# 1541-3n.net
KiCad netlist of a schematic drawn in EAGLE
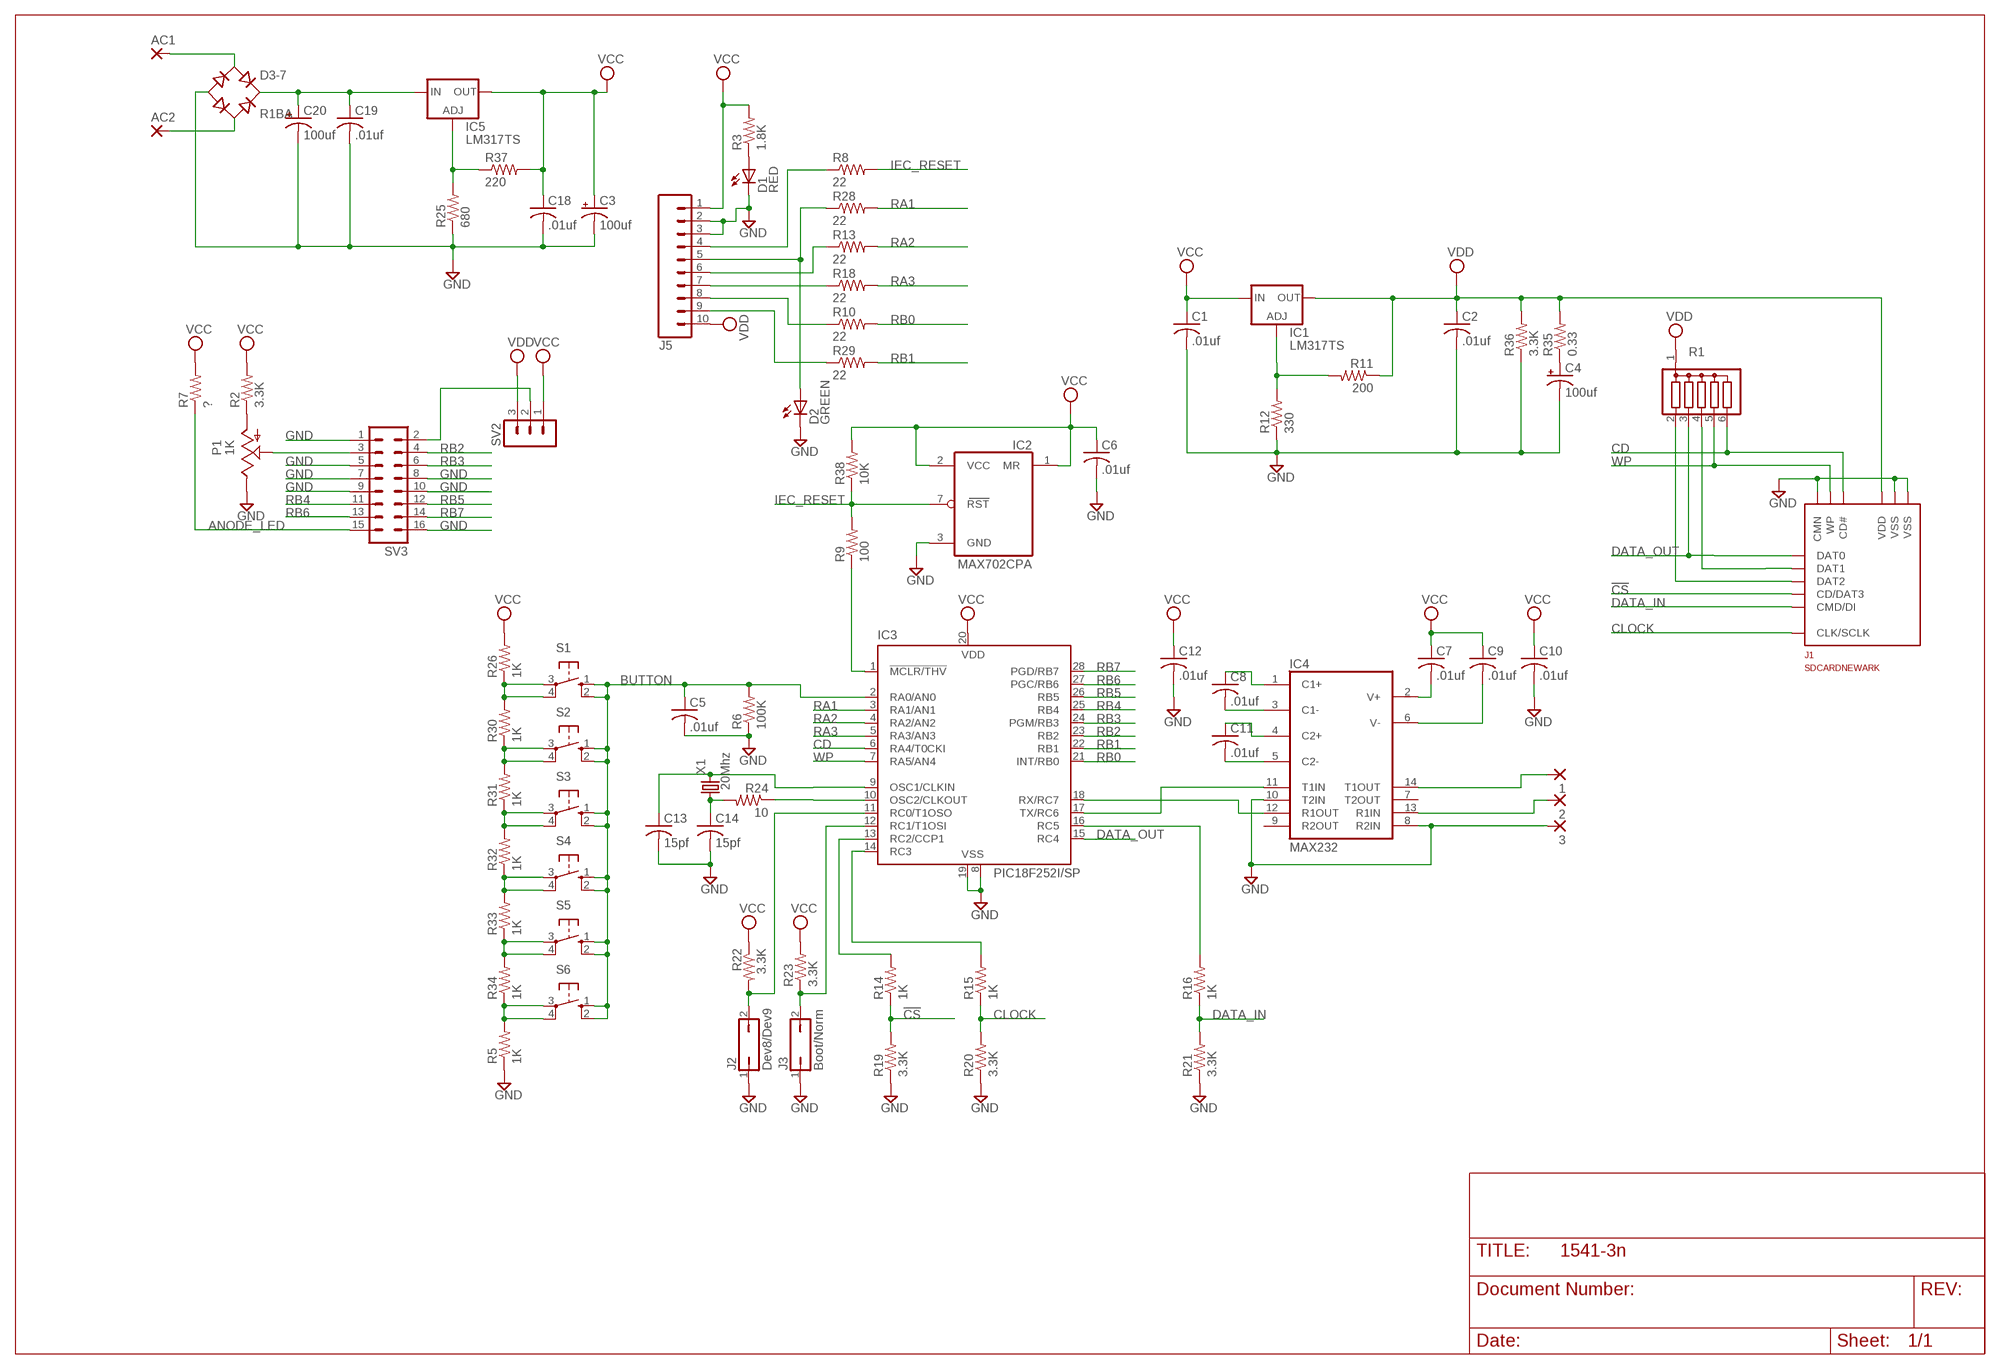
[diagram p0: schematic, sheet 1]

(export (version "E")
  (design (tool "Eeschema 10.0.6"))
  (components
    (comp (ref "1")
      (value "2,15/1,0")
      (footprint "eagle-import:2,15_1,0")
      (libsource (lib "eagle-import") (part "2,15/1,0"))
    )
    (comp (ref "2")
      (value "2,15/1,0")
      (footprint "eagle-import:2,15_1,0")
      (libsource (lib "eagle-import") (part "2,15/1,0"))
    )
    (comp (ref "3")
      (value "2,15/1,0")
      (footprint "eagle-import:2,15_1,0")
      (libsource (lib "eagle-import") (part "2,15/1,0"))
    )
    (comp (ref "AC1")
      (value "2,15/1,0")
      (footprint "eagle-import:2,15_1,0")
      (libsource (lib "eagle-import") (part "2,15/1,0"))
    )
    (comp (ref "AC2")
      (value "2,15/1,0")
      (footprint "eagle-import:2,15_1,0")
      (libsource (lib "eagle-import") (part "2,15/1,0"))
    )
    (comp (ref "C1")
      (value ".01uf")
      (footprint "eagle-import:C025-024X044")
      (libsource (lib "eagle-import") (part "C-US025-024X044"))
    )
    (comp (ref "C2")
      (value ".01uf")
      (footprint "eagle-import:C025-024X044")
      (libsource (lib "eagle-import") (part "C-US025-024X044"))
    )
    (comp (ref "C3")
      (value "100uf")
      (footprint "eagle-import:E2-5")
      (libsource (lib "eagle-import") (part "CPOL-USE2-5"))
    )
    (comp (ref "C4")
      (value "100uf")
      (footprint "eagle-import:E2-5")
      (libsource (lib "eagle-import") (part "CPOL-USE2-5"))
    )
    (comp (ref "C5")
      (value ".01uf")
      (footprint "eagle-import:C025-024X044")
      (libsource (lib "eagle-import") (part "C-US025-024X044"))
    )
    (comp (ref "C6")
      (value ".01uf")
      (footprint "eagle-import:C025-024X044")
      (libsource (lib "eagle-import") (part "C-US025-024X044"))
    )
    (comp (ref "C7")
      (value ".01uf")
      (footprint "eagle-import:C025-024X044")
      (libsource (lib "eagle-import") (part "C-US025-024X044"))
    )
    (comp (ref "C8")
      (value ".01uf")
      (footprint "eagle-import:C025-024X044")
      (libsource (lib "eagle-import") (part "C-US025-024X044"))
    )
    (comp (ref "C9")
      (value ".01uf")
      (footprint "eagle-import:C025-024X044")
      (libsource (lib "eagle-import") (part "C-US025-024X044"))
    )
    (comp (ref "C10")
      (value ".01uf")
      (footprint "eagle-import:C025-024X044")
      (libsource (lib "eagle-import") (part "C-US025-024X044"))
    )
    (comp (ref "C11")
      (value ".01uf")
      (footprint "eagle-import:C025-024X044")
      (libsource (lib "eagle-import") (part "C-US025-024X044"))
    )
    (comp (ref "C12")
      (value ".01uf")
      (footprint "eagle-import:C025-024X044")
      (libsource (lib "eagle-import") (part "C-US025-024X044"))
    )
    (comp (ref "C13")
      (value "15pf")
      (footprint "eagle-import:C025-024X044")
      (libsource (lib "eagle-import") (part "C-US025-024X044"))
    )
    (comp (ref "C14")
      (value "15pf")
      (footprint "eagle-import:C025-024X044")
      (libsource (lib "eagle-import") (part "C-US025-024X044"))
    )
    (comp (ref "C18")
      (value ".01uf")
      (footprint "eagle-import:C025-024X044")
      (libsource (lib "eagle-import") (part "C-US025-024X044"))
    )
    (comp (ref "C19")
      (value ".01uf")
      (footprint "eagle-import:C025-024X044")
      (libsource (lib "eagle-import") (part "C-US025-024X044"))
    )
    (comp (ref "C20")
      (value "100uf")
      (footprint "eagle-import:E2-5")
      (libsource (lib "eagle-import") (part "CPOL-USE2-5"))
    )
    (comp (ref "D1")
      (value "RED")
      (footprint "eagle-import:LED3MM")
      (libsource (lib "eagle-import") (part "LED3MM"))
    )
    (comp (ref "D2")
      (value "GREEN")
      (footprint "eagle-import:LED3MM")
      (libsource (lib "eagle-import") (part "LED3MM"))
    )
    (comp (ref "D3-7")
      (value "R1BA")
      (footprint "eagle-import:RB1A")
      (libsource (lib "eagle-import") (part "RB1A"))
    )
    (comp (ref "IC1")
      (value "LM317TS")
      (footprint "eagle-import:317TS")
      (libsource (lib "eagle-import") (part "LM317TS"))
    )
    (comp (ref "IC2")
      (value "MAX702CPA")
      (footprint "eagle-import:DIL08")
      (fields (field (name "MF") "MAXIM") (field (name "MPN") "MAX702CPA+"))
      (libsource (lib "eagle-import") (part "MAX702CPA"))
    )
    (comp (ref "IC3")
      (value "PIC18F252I/SP")
      (footprint "eagle-import:DIL28-3")
      (fields (field (name "MF") "MICROCHIP") (field (name "MPN") "PIC16F870-I/SP"))
      (libsource (lib "eagle-import") (part "PIC16870PF"))
    )
    (comp (ref "IC4")
      (value "MAX232")
      (footprint "eagle-import:DIL16")
      (fields (field (name "MF") "MAXIM") (field (name "MPN") "MAX232ACPE+"))
      (libsource (lib "eagle-import") (part "MAX232"))
    )
    (comp (ref "IC5")
      (value "LM317TS")
      (footprint "eagle-import:317TS")
      (libsource (lib "eagle-import") (part "LM317TS"))
    )
    (comp (ref "J1")
      (value "SDCARDNEWARK")
      (footprint "eagle-import:SDBMF-00915B0T2")
      (libsource (lib "eagle-import") (part "SDCARDNEWARK"))
    )
    (comp (ref "J2")
      (value "Dev8/Dev9")
      (footprint "eagle-import:JP1")
      (libsource (lib "eagle-import") (part "JP1Q"))
    )
    (comp (ref "J3")
      (value "Boot/Norm")
      (footprint "eagle-import:JP1")
      (libsource (lib "eagle-import") (part "JP1Q"))
    )
    (comp (ref "J5")
      (value "M10")
      (footprint "eagle-import:10P")
      (libsource (lib "eagle-import") (part "M10"))
    )
    (comp (ref "P1")
      (value "1K")
      (footprint "eagle-import:LI10")
      (libsource (lib "eagle-import") (part "TRIM_US-LI10"))
    )
    (comp (ref "R1")
      (value "G05R")
      (footprint "eagle-import:SIL6")
      (libsource (lib "eagle-import") (part "G05R"))
    )
    (comp (ref "R2")
      (value "3.3K")
      (footprint "eagle-import:0207_2V")
      (libsource (lib "eagle-import") (part "R-US_0207/2V"))
    )
    (comp (ref "R3")
      (value "1.8K")
      (footprint "eagle-import:0207_2V")
      (libsource (lib "eagle-import") (part "R-US_0207/2V"))
    )
    (comp (ref "R5")
      (value "1K")
      (footprint "eagle-import:0207_2V")
      (libsource (lib "eagle-import") (part "R-US_0207/2V"))
    )
    (comp (ref "R6")
      (value "100K")
      (footprint "eagle-import:0207_2V")
      (libsource (lib "eagle-import") (part "R-US_0207/2V"))
    )
    (comp (ref "R7")
      (value "?")
      (footprint "eagle-import:0207_2V")
      (libsource (lib "eagle-import") (part "R-US_0207/2V"))
    )
    (comp (ref "R8")
      (value "22")
      (footprint "eagle-import:0207_2V")
      (libsource (lib "eagle-import") (part "R-US_0207/2V"))
    )
    (comp (ref "R9")
      (value "100")
      (footprint "eagle-import:0207_2V")
      (libsource (lib "eagle-import") (part "R-US_0207/2V"))
    )
    (comp (ref "R10")
      (value "22")
      (footprint "eagle-import:0207_2V")
      (libsource (lib "eagle-import") (part "R-US_0207/2V"))
    )
    (comp (ref "R11")
      (value "200")
      (footprint "eagle-import:0207_2V")
      (libsource (lib "eagle-import") (part "R-US_0207/2V"))
    )
    (comp (ref "R12")
      (value "330")
      (footprint "eagle-import:0207_2V")
      (libsource (lib "eagle-import") (part "R-US_0207/2V"))
    )
    (comp (ref "R13")
      (value "22")
      (footprint "eagle-import:0207_2V")
      (libsource (lib "eagle-import") (part "R-US_0207/2V"))
    )
    (comp (ref "R14")
      (value "1K")
      (footprint "eagle-import:0207_2V")
      (libsource (lib "eagle-import") (part "R-US_0207/2V"))
    )
    (comp (ref "R15")
      (value "1K")
      (footprint "eagle-import:0207_2V")
      (libsource (lib "eagle-import") (part "R-US_0207/2V"))
    )
    (comp (ref "R16")
      (value "1K")
      (footprint "eagle-import:0207_2V")
      (libsource (lib "eagle-import") (part "R-US_0207/2V"))
    )
    (comp (ref "R18")
      (value "22")
      (footprint "eagle-import:0207_2V")
      (libsource (lib "eagle-import") (part "R-US_0207/2V"))
    )
    (comp (ref "R19")
      (value "3.3K")
      (footprint "eagle-import:0207_2V")
      (libsource (lib "eagle-import") (part "R-US_0207/2V"))
    )
    (comp (ref "R20")
      (value "3.3K")
      (footprint "eagle-import:0207_2V")
      (libsource (lib "eagle-import") (part "R-US_0207/2V"))
    )
    (comp (ref "R21")
      (value "3.3K")
      (footprint "eagle-import:0207_2V")
      (libsource (lib "eagle-import") (part "R-US_0207/2V"))
    )
    (comp (ref "R22")
      (value "3.3K")
      (footprint "eagle-import:0207_2V")
      (libsource (lib "eagle-import") (part "R-US_0207/2V"))
    )
    (comp (ref "R23")
      (value "3.3K")
      (footprint "eagle-import:0207_2V")
      (libsource (lib "eagle-import") (part "R-US_0207/2V"))
    )
    (comp (ref "R24")
      (value "10")
      (footprint "eagle-import:0207_2V")
      (libsource (lib "eagle-import") (part "R-US_0207/2V"))
    )
    (comp (ref "R25")
      (value "680")
      (footprint "eagle-import:0207_2V")
      (libsource (lib "eagle-import") (part "R-US_0207/2V"))
    )
    (comp (ref "R26")
      (value "1K")
      (footprint "eagle-import:0207_2V")
      (libsource (lib "eagle-import") (part "R-US_0207/2V"))
    )
    (comp (ref "R28")
      (value "22")
      (footprint "eagle-import:0207_2V")
      (libsource (lib "eagle-import") (part "R-US_0207/2V"))
    )
    (comp (ref "R29")
      (value "22")
      (footprint "eagle-import:0207_2V")
      (libsource (lib "eagle-import") (part "R-US_0207/2V"))
    )
    (comp (ref "R30")
      (value "1K")
      (footprint "eagle-import:0207_2V")
      (libsource (lib "eagle-import") (part "R-US_0207/2V"))
    )
    (comp (ref "R31")
      (value "1K")
      (footprint "eagle-import:0207_2V")
      (libsource (lib "eagle-import") (part "R-US_0207/2V"))
    )
    (comp (ref "R32")
      (value "1K")
      (footprint "eagle-import:0207_2V")
      (libsource (lib "eagle-import") (part "R-US_0207/2V"))
    )
    (comp (ref "R33")
      (value "1K")
      (footprint "eagle-import:0207_2V")
      (libsource (lib "eagle-import") (part "R-US_0207/2V"))
    )
    (comp (ref "R34")
      (value "1K")
      (footprint "eagle-import:0207_2V")
      (libsource (lib "eagle-import") (part "R-US_0207/2V"))
    )
    (comp (ref "R35")
      (value "0.33")
      (footprint "eagle-import:0207_2V")
      (libsource (lib "eagle-import") (part "R-US_0207/2V"))
    )
    (comp (ref "R36")
      (value "3.3K")
      (footprint "eagle-import:0207_2V")
      (libsource (lib "eagle-import") (part "R-US_0207/2V"))
    )
    (comp (ref "R37")
      (value "220")
      (footprint "eagle-import:0207_2V")
      (libsource (lib "eagle-import") (part "R-US_0207/2V"))
    )
    (comp (ref "R38")
      (value "10K")
      (footprint "eagle-import:0207_2V")
      (libsource (lib "eagle-import") (part "R-US_0207/2V"))
    )
    (comp (ref "S1")
      (value "10-XX")
      (footprint "eagle-import:B3F-10XX")
      (fields (field (name "MPN") "B3F-1000"))
      (libsource (lib "eagle-import") (part "10-XX"))
    )
    (comp (ref "S2")
      (value "10-XX")
      (footprint "eagle-import:B3F-10XX")
      (fields (field (name "MPN") "B3F-1000"))
      (libsource (lib "eagle-import") (part "10-XX"))
    )
    (comp (ref "S3")
      (value "10-XX")
      (footprint "eagle-import:B3F-10XX")
      (fields (field (name "MPN") "B3F-1000"))
      (libsource (lib "eagle-import") (part "10-XX"))
    )
    (comp (ref "S4")
      (value "10-XX")
      (footprint "eagle-import:B3F-10XX")
      (fields (field (name "MPN") "B3F-1000"))
      (libsource (lib "eagle-import") (part "10-XX"))
    )
    (comp (ref "S5")
      (value "10-XX")
      (footprint "eagle-import:B3F-10XX")
      (fields (field (name "MPN") "B3F-1000"))
      (libsource (lib "eagle-import") (part "10-XX"))
    )
    (comp (ref "S6")
      (value "10-XX")
      (footprint "eagle-import:B3F-10XX")
      (fields (field (name "MPN") "B3F-1000"))
      (libsource (lib "eagle-import") (part "10-XX"))
    )
    (comp (ref "SV2")
      (value "MA03-1")
      (footprint "eagle-import:MA03-1")
      (libsource (lib "eagle-import") (part "MA03-1"))
    )
    (comp (ref "SV3")
      (value "ML16")
      (footprint "eagle-import:ML16")
      (libsource (lib "eagle-import") (part "ML16"))
    )
    (comp (ref "X1")
      (value "20Mhz")
      (footprint "eagle-import:HC49U70")
      (libsource (lib "eagle-import") (part "CRYSTALHC49U70"))
    )
  )
  (nets
    (net (code "1") (name "/ANODE_LED") (class "Default")
      (node (ref "R7") (pin "1") (pinfunction "1_1") (pintype "passive"))
      (node (ref "SV3") (pin "15") (pinfunction "15_15") (pintype "passive"))
    )
    (net (code "2") (name "/BUTTON") (class "Default")
      (node (ref "C5") (pin "1") (pinfunction "1_1") (pintype "passive"))
      (node (ref "IC3") (pin "2") (pinfunction "RA0/AN0_2") (pintype "bidirectional"))
      (node (ref "R6") (pin "2") (pinfunction "2_2") (pintype "passive"))
      (node (ref "S1") (pin "1") (pinfunction "S_1") (pintype "passive"))
      (node (ref "S1") (pin "2") (pinfunction "S1_2") (pintype "passive"))
      (node (ref "S2") (pin "1") (pinfunction "S_1") (pintype "passive"))
      (node (ref "S2") (pin "2") (pinfunction "S1_2") (pintype "passive"))
      (node (ref "S3") (pin "1") (pinfunction "S_1") (pintype "passive"))
      (node (ref "S3") (pin "2") (pinfunction "S1_2") (pintype "passive"))
      (node (ref "S4") (pin "1") (pinfunction "S_1") (pintype "passive"))
      (node (ref "S4") (pin "2") (pinfunction "S1_2") (pintype "passive"))
      (node (ref "S5") (pin "1") (pinfunction "S_1") (pintype "passive"))
      (node (ref "S5") (pin "2") (pinfunction "S1_2") (pintype "passive"))
      (node (ref "S6") (pin "1") (pinfunction "S_1") (pintype "passive"))
      (node (ref "S6") (pin "2") (pinfunction "S1_2") (pintype "passive"))
    )
    (net (code "3") (name "/CD") (class "Default")
      (node (ref "IC3") (pin "6") (pinfunction "RA4/T0CKI_6") (pintype "bidirectional"))
      (node (ref "J1") (pin "SW1") (pinfunction "CD#_SW1") (pintype "output"))
      (node (ref "R1") (pin "6") (pinfunction "6_6") (pintype "passive"))
    )
    (net (code "4") (name "/CLOCK") (class "Default")
      (node (ref "J1") (pin "CLK") (pinfunction "CLK/SCLK_CLK") (pintype "bidirectional"))
      (node (ref "R15") (pin "1") (pinfunction "1_1") (pintype "passive"))
      (node (ref "R20") (pin "2") (pinfunction "2_2") (pintype "passive"))
    )
    (net (code "5") (name "/DATA_IN") (class "Default")
      (node (ref "J1") (pin "CMD") (pinfunction "CMD/DI_CMD") (pintype "bidirectional"))
      (node (ref "R16") (pin "1") (pinfunction "1_1") (pintype "passive"))
      (node (ref "R21") (pin "2") (pinfunction "2_2") (pintype "passive"))
    )
    (net (code "6") (name "/DATA_OUT") (class "Default")
      (node (ref "IC3") (pin "15") (pinfunction "RC4_15") (pintype "bidirectional"))
      (node (ref "J1") (pin "DAT0") (pinfunction "DAT0_DAT0") (pintype "bidirectional"))
      (node (ref "R1") (pin "3") (pinfunction "3_3") (pintype "passive"))
    )
    (net (code "7") (name "/IEC_RESET") (class "Default")
      (node (ref "IC2") (pin "7") (pinfunction "RST_7") (pintype "output"))
      (node (ref "R38") (pin "1") (pinfunction "1_1") (pintype "passive"))
      (node (ref "R8") (pin "2") (pinfunction "2_2") (pintype "passive"))
      (node (ref "R9") (pin "2") (pinfunction "2_2") (pintype "passive"))
    )
    (net (code "8") (name "/RA1") (class "Default")
      (node (ref "IC3") (pin "3") (pinfunction "RA1/AN1_3") (pintype "bidirectional"))
      (node (ref "R28") (pin "2") (pinfunction "2_2") (pintype "passive"))
    )
    (net (code "9") (name "/RA2") (class "Default")
      (node (ref "IC3") (pin "4") (pinfunction "RA2/AN2_4") (pintype "bidirectional"))
      (node (ref "R13") (pin "2") (pinfunction "2_2") (pintype "passive"))
    )
    (net (code "10") (name "/RA3") (class "Default")
      (node (ref "IC3") (pin "5") (pinfunction "RA3/AN3_5") (pintype "bidirectional"))
      (node (ref "R18") (pin "2") (pinfunction "2_2") (pintype "passive"))
    )
    (net (code "11") (name "/RB0") (class "Default")
      (node (ref "IC3") (pin "21") (pinfunction "INT/RB0_21") (pintype "bidirectional"))
      (node (ref "R10") (pin "2") (pinfunction "2_2") (pintype "passive"))
    )
    (net (code "12") (name "/RB1") (class "Default")
      (node (ref "IC3") (pin "22") (pinfunction "RB1_22") (pintype "bidirectional"))
      (node (ref "R29") (pin "2") (pinfunction "2_2") (pintype "passive"))
    )
    (net (code "13") (name "/RB2") (class "Default")
      (node (ref "IC3") (pin "23") (pinfunction "RB2_23") (pintype "bidirectional"))
      (node (ref "SV3") (pin "4") (pinfunction "4_4") (pintype "passive"))
    )
    (net (code "14") (name "/RB3") (class "Default")
      (node (ref "IC3") (pin "24") (pinfunction "PGM/RB3_24") (pintype "bidirectional"))
      (node (ref "SV3") (pin "6") (pinfunction "6_6") (pintype "passive"))
    )
    (net (code "15") (name "/RB4") (class "Default")
      (node (ref "IC3") (pin "25") (pinfunction "RB4_25") (pintype "bidirectional"))
      (node (ref "SV3") (pin "11") (pinfunction "11_11") (pintype "passive"))
    )
    (net (code "16") (name "/RB5") (class "Default")
      (node (ref "IC3") (pin "26") (pinfunction "RB5_26") (pintype "bidirectional"))
      (node (ref "SV3") (pin "12") (pinfunction "12_12") (pintype "passive"))
    )
    (net (code "17") (name "/RB6") (class "Default")
      (node (ref "IC3") (pin "27") (pinfunction "PGC/RB6_27") (pintype "bidirectional"))
      (node (ref "SV3") (pin "13") (pinfunction "13_13") (pintype "passive"))
    )
    (net (code "18") (name "/RB7") (class "Default")
      (node (ref "IC3") (pin "28") (pinfunction "PGD/RB7_28") (pintype "bidirectional"))
      (node (ref "SV3") (pin "14") (pinfunction "14_14") (pintype "passive"))
    )
    (net (code "19") (name "/WP") (class "Default")
      (node (ref "IC3") (pin "7") (pinfunction "RA5/AN4_7") (pintype "bidirectional"))
      (node (ref "J1") (pin "SW2") (pinfunction "WP_SW2") (pintype "output"))
      (node (ref "R1") (pin "5") (pinfunction "5_5") (pintype "passive"))
    )
    (net (code "20") (name "/~{CS}") (class "Default")
      (node (ref "J1") (pin "DAT3") (pinfunction "CD/DAT3_DAT3") (pintype "bidirectional"))
      (node (ref "R14") (pin "1") (pinfunction "1_1") (pintype "passive"))
      (node (ref "R19") (pin "2") (pinfunction "2_2") (pintype "passive"))
    )
    (net (code "21") (name "GND") (class "Default")
      (node (ref "3") (pin "1") (pinfunction "P_1") (pintype "passive"))
      (node (ref "C1") (pin "2") (pinfunction "2_2") (pintype "passive"))
      (node (ref "C10") (pin "2") (pinfunction "2_2") (pintype "passive"))
      (node (ref "C12") (pin "2") (pinfunction "2_2") (pintype "passive"))
      (node (ref "C13") (pin "2") (pinfunction "2_2") (pintype "passive"))
      (node (ref "C14") (pin "2") (pinfunction "2_2") (pintype "passive"))
      (node (ref "C18") (pin "2") (pinfunction "2_2") (pintype "passive"))
      (node (ref "C19") (pin "2") (pinfunction "2_2") (pintype "passive"))
      (node (ref "C2") (pin "2") (pinfunction "2_2") (pintype "passive"))
      (node (ref "C20") (pin "-") (pinfunction "-_-") (pintype "passive"))
      (node (ref "C3") (pin "-") (pinfunction "-_-") (pintype "passive"))
      (node (ref "C4") (pin "-") (pinfunction "-_-") (pintype "passive"))
      (node (ref "C5") (pin "2") (pinfunction "2_2") (pintype "passive"))
      (node (ref "C6") (pin "2") (pinfunction "2_2") (pintype "passive"))
      (node (ref "D1") (pin "K") (pinfunction "C_K") (pintype "passive"))
      (node (ref "D2") (pin "K") (pinfunction "C_K") (pintype "passive"))
      (node (ref "D3-7") (pin "-") (pinfunction "-_-") (pintype "passive"))
      (node (ref "IC2") (pin "3") (pinfunction "GND_3") (pintype "power_in"))
      (node (ref "IC3") (pin "19") (pinfunction "VSS_19") (pintype "power_in"))
      (node (ref "IC3") (pin "8") (pinfunction "VSS_8") (pintype "power_in"))
      (node (ref "IC4") (pin "10") (pinfunction "T2IN_10") (pintype "input"))
      (node (ref "IC4") (pin "8") (pinfunction "R2IN_8") (pintype "input"))
      (node (ref "J1") (pin "SW3") (pinfunction "CMN_SW3") (pintype "input"))
      (node (ref "J1") (pin "VSS$1") (pinfunction "VSS_VSS$1") (pintype "power_in"))
      (node (ref "J1") (pin "VSS$2") (pinfunction "VSS_VSS$2") (pintype "power_in"))
      (node (ref "J2") (pin "1") (pinfunction "1_1") (pintype "passive"))
      (node (ref "J3") (pin "1") (pinfunction "1_1") (pintype "passive"))
      (node (ref "J5") (pin "2") (pinfunction "2_2") (pintype "passive"))
      (node (ref "J5") (pin "3") (pinfunction "3_3") (pintype "passive"))
      (node (ref "P1") (pin "E") (pinfunction "E_E") (pintype "passive"))
      (node (ref "R12") (pin "1") (pinfunction "1_1") (pintype "passive"))
      (node (ref "R19") (pin "1") (pinfunction "1_1") (pintype "passive"))
      (node (ref "R20") (pin "1") (pinfunction "1_1") (pintype "passive"))
      (node (ref "R21") (pin "1") (pinfunction "1_1") (pintype "passive"))
      (node (ref "R25") (pin "1") (pinfunction "1_1") (pintype "passive"))
      (node (ref "R36") (pin "1") (pinfunction "1_1") (pintype "passive"))
      (node (ref "R5") (pin "1") (pinfunction "1_1") (pintype "passive"))
      (node (ref "R6") (pin "1") (pinfunction "1_1") (pintype "passive"))
      (node (ref "SV3") (pin "1") (pinfunction "1_1") (pintype "passive"))
      (node (ref "SV3") (pin "10") (pinfunction "10_10") (pintype "passive"))
      (node (ref "SV3") (pin "16") (pinfunction "16_16") (pintype "passive"))
      (node (ref "SV3") (pin "5") (pinfunction "5_5") (pintype "passive"))
      (node (ref "SV3") (pin "7") (pinfunction "7_7") (pintype "passive"))
      (node (ref "SV3") (pin "8") (pinfunction "8_8") (pintype "passive"))
      (node (ref "SV3") (pin "9") (pinfunction "9_9") (pintype "passive"))
    )
    (net (code "22") (name "Net-(1-P)") (class "Default")
      (node (ref "1") (pin "1") (pinfunction "P_1") (pintype "passive"))
      (node (ref "IC4") (pin "14") (pinfunction "T1OUT_14") (pintype "output"))
    )
    (net (code "23") (name "Net-(2-P)") (class "Default")
      (node (ref "2") (pin "1") (pinfunction "P_1") (pintype "passive"))
      (node (ref "IC4") (pin "13") (pinfunction "R1IN_13") (pintype "input"))
    )
    (net (code "24") (name "Net-(AC1-P)") (class "Default")
      (node (ref "AC1") (pin "1") (pinfunction "P_1") (pintype "passive"))
      (node (ref "D3-7") (pin "AC1") (pinfunction "AC1_AC1") (pintype "passive"))
    )
    (net (code "25") (name "Net-(AC2-P)") (class "Default")
      (node (ref "AC2") (pin "1") (pinfunction "P_1") (pintype "passive"))
      (node (ref "D3-7") (pin "AC2") (pinfunction "AC2_AC2") (pintype "passive"))
    )
    (net (code "26") (name "Net-(C4-Pad+)") (class "Default")
      (node (ref "C4") (pin "+") (pinfunction "+_+") (pintype "passive"))
      (node (ref "R35") (pin "1") (pinfunction "1_1") (pintype "passive"))
    )
    (net (code "27") (name "Net-(C14-Pad1)") (class "Default")
      (node (ref "C14") (pin "1") (pinfunction "1_1") (pintype "passive"))
      (node (ref "R24") (pin "2") (pinfunction "2_2") (pintype "passive"))
      (node (ref "X1") (pin "1") (pinfunction "1_1") (pintype "passive"))
    )
    (net (code "28") (name "Net-(D1-PadA)") (class "Default")
      (node (ref "D1") (pin "A") (pinfunction "A_A") (pintype "passive"))
      (node (ref "R3") (pin "1") (pinfunction "1_1") (pintype "passive"))
    )
    (net (code "29") (name "Net-(D2-PadA)") (class "Default")
      (node (ref "D2") (pin "A") (pinfunction "A_A") (pintype "passive"))
      (node (ref "J5") (pin "5") (pinfunction "5_5") (pintype "passive"))
      (node (ref "R28") (pin "1") (pinfunction "1_1") (pintype "passive"))
    )
    (net (code "30") (name "Net-(IC1-ADJ)") (class "Default")
      (node (ref "IC1") (pin "1") (pinfunction "ADJ_1") (pintype "input"))
      (node (ref "R11") (pin "2") (pinfunction "2_2") (pintype "passive"))
      (node (ref "R12") (pin "2") (pinfunction "2_2") (pintype "passive"))
    )
    (net (code "31") (name "Net-(IC3-OSC1{slash}CLKIN)") (class "Default")
      (node (ref "C13") (pin "1") (pinfunction "1_1") (pintype "passive"))
      (node (ref "IC3") (pin "9") (pinfunction "OSC1/CLKIN_9") (pintype "input"))
      (node (ref "X1") (pin "2") (pinfunction "2_2") (pintype "passive"))
    )
    (net (code "32") (name "Net-(IC3-OSC2{slash}CLKOUT)") (class "Default")
      (node (ref "IC3") (pin "10") (pinfunction "OSC2/CLKOUT_10") (pintype "output"))
      (node (ref "R24") (pin "1") (pinfunction "1_1") (pintype "passive"))
    )
    (net (code "33") (name "Net-(IC3-RC0{slash}T1OSO)") (class "Default")
      (node (ref "IC3") (pin "11") (pinfunction "RC0/T1OSO_11") (pintype "bidirectional"))
      (node (ref "J2") (pin "2") (pinfunction "2_2") (pintype "passive"))
      (node (ref "R22") (pin "2") (pinfunction "2_2") (pintype "passive"))
    )
    (net (code "34") (name "Net-(IC3-RC1{slash}T1OSI)") (class "Default")
      (node (ref "IC3") (pin "12") (pinfunction "RC1/T1OSI_12") (pintype "bidirectional"))
      (node (ref "J3") (pin "2") (pinfunction "2_2") (pintype "passive"))
      (node (ref "R23") (pin "1") (pinfunction "1_1") (pintype "passive"))
    )
    (net (code "35") (name "Net-(IC3-RC2{slash}CCP1)") (class "Default")
      (node (ref "IC3") (pin "13") (pinfunction "RC2/CCP1_13") (pintype "bidirectional"))
      (node (ref "R14") (pin "2") (pinfunction "2_2") (pintype "passive"))
    )
    (net (code "36") (name "Net-(IC3-RC3)") (class "Default")
      (node (ref "IC3") (pin "14") (pinfunction "RC3_14") (pintype "bidirectional"))
      (node (ref "R15") (pin "2") (pinfunction "2_2") (pintype "passive"))
    )
    (net (code "37") (name "Net-(IC3-RC5)") (class "Default")
      (node (ref "IC3") (pin "16") (pinfunction "RC5_16") (pintype "bidirectional"))
      (node (ref "R16") (pin "2") (pinfunction "2_2") (pintype "passive"))
    )
    (net (code "38") (name "Net-(IC3-RX{slash}RC7)") (class "Default")
      (node (ref "IC3") (pin "18") (pinfunction "RX/RC7_18") (pintype "bidirectional"))
      (node (ref "IC4") (pin "12") (pinfunction "R1OUT_12") (pintype "output"))
    )
    (net (code "39") (name "Net-(IC3-TX{slash}RC6)") (class "Default")
      (node (ref "IC3") (pin "17") (pinfunction "TX/RC6_17") (pintype "bidirectional"))
      (node (ref "IC4") (pin "11") (pinfunction "T1IN_11") (pintype "input"))
    )
    (net (code "40") (name "Net-(IC3-~{MCLR{slash}THV})") (class "Default")
      (node (ref "IC3") (pin "1") (pinfunction "~{MCLR/THV}_1") (pintype "input"))
      (node (ref "R9") (pin "1") (pinfunction "1_1") (pintype "passive"))
    )
    (net (code "41") (name "Net-(IC4A-C1+)") (class "Default")
      (node (ref "C8") (pin "1") (pinfunction "1_1") (pintype "passive"))
      (node (ref "IC4") (pin "1") (pinfunction "C1+_1") (pintype "bidirectional"))
    )
    (net (code "42") (name "Net-(IC4A-C1-)") (class "Default")
      (node (ref "C8") (pin "2") (pinfunction "2_2") (pintype "passive"))
      (node (ref "IC4") (pin "3") (pinfunction "C1-_3") (pintype "bidirectional"))
    )
    (net (code "43") (name "Net-(IC4A-C2+)") (class "Default")
      (node (ref "C11") (pin "1") (pinfunction "1_1") (pintype "passive"))
      (node (ref "IC4") (pin "4") (pinfunction "C2+_4") (pintype "bidirectional"))
    )
    (net (code "44") (name "Net-(IC4A-C2-)") (class "Default")
      (node (ref "C11") (pin "2") (pinfunction "2_2") (pintype "passive"))
      (node (ref "IC4") (pin "5") (pinfunction "C2-_5") (pintype "bidirectional"))
    )
    (net (code "45") (name "Net-(IC4A-V+)") (class "Default")
      (node (ref "C7") (pin "2") (pinfunction "2_2") (pintype "passive"))
      (node (ref "IC4") (pin "2") (pinfunction "V+_2") (pintype "bidirectional"))
    )
    (net (code "46") (name "Net-(IC4A-V-)") (class "Default")
      (node (ref "C9") (pin "2") (pinfunction "2_2") (pintype "passive"))
      (node (ref "IC4") (pin "6") (pinfunction "V-_6") (pintype "bidirectional"))
    )
    (net (code "47") (name "Net-(IC5-ADJ)") (class "Default")
      (node (ref "IC5") (pin "1") (pinfunction "ADJ_1") (pintype "input"))
      (node (ref "R25") (pin "2") (pinfunction "2_2") (pintype "passive"))
      (node (ref "R37") (pin "1") (pinfunction "1_1") (pintype "passive"))
    )
    (net (code "48") (name "Net-(IC5-IN)") (class "Default")
      (node (ref "C19") (pin "1") (pinfunction "1_1") (pintype "passive"))
      (node (ref "C20") (pin "+") (pinfunction "+_+") (pintype "passive"))
      (node (ref "D3-7") (pin "+") (pinfunction "+_+") (pintype "passive"))
      (node (ref "IC5") (pin "3") (pinfunction "IN_3") (pintype "input"))
    )
    (net (code "49") (name "Net-(J1-PadDAT1)") (class "Default")
      (node (ref "J1") (pin "DAT1") (pinfunction "DAT1_DAT1") (pintype "bidirectional"))
      (node (ref "R1") (pin "4") (pinfunction "4_4") (pintype "passive"))
    )
    (net (code "50") (name "Net-(J1-PadDAT2)") (class "Default")
      (node (ref "J1") (pin "DAT2") (pinfunction "DAT2_DAT2") (pintype "bidirectional"))
      (node (ref "R1") (pin "2") (pinfunction "2_2") (pintype "passive"))
    )
    (net (code "51") (name "Net-(J5-Pad4)") (class "Default")
      (node (ref "J5") (pin "4") (pinfunction "4_4") (pintype "passive"))
      (node (ref "R8") (pin "1") (pinfunction "1_1") (pintype "passive"))
    )
    (net (code "52") (name "Net-(J5-Pad6)") (class "Default")
      (node (ref "J5") (pin "6") (pinfunction "6_6") (pintype "passive"))
      (node (ref "R13") (pin "1") (pinfunction "1_1") (pintype "passive"))
    )
    (net (code "53") (name "Net-(J5-Pad7)") (class "Default")
      (node (ref "J5") (pin "7") (pinfunction "7_7") (pintype "passive"))
      (node (ref "R18") (pin "1") (pinfunction "1_1") (pintype "passive"))
    )
    (net (code "54") (name "Net-(J5-Pad8)") (class "Default")
      (node (ref "J5") (pin "8") (pinfunction "8_8") (pintype "passive"))
      (node (ref "R10") (pin "1") (pinfunction "1_1") (pintype "passive"))
    )
    (net (code "55") (name "Net-(J5-Pad9)") (class "Default")
      (node (ref "J5") (pin "9") (pinfunction "9_9") (pintype "passive"))
      (node (ref "R29") (pin "1") (pinfunction "1_1") (pintype "passive"))
    )
    (net (code "56") (name "Net-(P1-PadA)") (class "Default")
      (node (ref "P1") (pin "A") (pinfunction "A_A") (pintype "passive"))
      (node (ref "R2") (pin "1") (pinfunction "1_1") (pintype "passive"))
    )
    (net (code "57") (name "Net-(P1-PadS)") (class "Default")
      (node (ref "P1") (pin "S") (pinfunction "S_S") (pintype "passive"))
      (node (ref "SV3") (pin "3") (pinfunction "3_3") (pintype "passive"))
    )
    (net (code "58") (name "Net-(S1-P)") (class "Default")
      (node (ref "R26") (pin "1") (pinfunction "1_1") (pintype "passive"))
      (node (ref "R30") (pin "2") (pinfunction "2_2") (pintype "passive"))
      (node (ref "S1") (pin "3") (pinfunction "P_3") (pintype "passive"))
      (node (ref "S1") (pin "4") (pinfunction "P1_4") (pintype "passive"))
    )
    (net (code "59") (name "Net-(S2-P)") (class "Default")
      (node (ref "R30") (pin "1") (pinfunction "1_1") (pintype "passive"))
      (node (ref "R31") (pin "2") (pinfunction "2_2") (pintype "passive"))
      (node (ref "S2") (pin "3") (pinfunction "P_3") (pintype "passive"))
      (node (ref "S2") (pin "4") (pinfunction "P1_4") (pintype "passive"))
    )
    (net (code "60") (name "Net-(S3-P)") (class "Default")
      (node (ref "R31") (pin "1") (pinfunction "1_1") (pintype "passive"))
      (node (ref "R32") (pin "2") (pinfunction "2_2") (pintype "passive"))
      (node (ref "S3") (pin "3") (pinfunction "P_3") (pintype "passive"))
      (node (ref "S3") (pin "4") (pinfunction "P1_4") (pintype "passive"))
    )
    (net (code "61") (name "Net-(S4-P)") (class "Default")
      (node (ref "R32") (pin "1") (pinfunction "1_1") (pintype "passive"))
      (node (ref "R33") (pin "2") (pinfunction "2_2") (pintype "passive"))
      (node (ref "S4") (pin "3") (pinfunction "P_3") (pintype "passive"))
      (node (ref "S4") (pin "4") (pinfunction "P1_4") (pintype "passive"))
    )
    (net (code "62") (name "Net-(S5-P)") (class "Default")
      (node (ref "R33") (pin "1") (pinfunction "1_1") (pintype "passive"))
      (node (ref "R34") (pin "2") (pinfunction "2_2") (pintype "passive"))
      (node (ref "S5") (pin "3") (pinfunction "P_3") (pintype "passive"))
      (node (ref "S5") (pin "4") (pinfunction "P1_4") (pintype "passive"))
    )
    (net (code "63") (name "Net-(S6-P)") (class "Default")
      (node (ref "R34") (pin "1") (pinfunction "1_1") (pintype "passive"))
      (node (ref "R5") (pin "2") (pinfunction "2_2") (pintype "passive"))
      (node (ref "S6") (pin "3") (pinfunction "P_3") (pintype "passive"))
      (node (ref "S6") (pin "4") (pinfunction "P1_4") (pintype "passive"))
    )
    (net (code "64") (name "Net-(SV2-Pad2)") (class "Default")
      (node (ref "SV2") (pin "2") (pinfunction "2_2") (pintype "passive"))
      (node (ref "SV3") (pin "2") (pinfunction "2_2") (pintype "passive"))
    )
    (net (code "65") (name "VCC") (class "Default")
      (node (ref "C1") (pin "1") (pinfunction "1_1") (pintype "passive"))
      (node (ref "C10") (pin "1") (pinfunction "1_1") (pintype "passive"))
      (node (ref "C12") (pin "1") (pinfunction "1_1") (pintype "passive"))
      (node (ref "C18") (pin "1") (pinfunction "1_1") (pintype "passive"))
      (node (ref "C3") (pin "+") (pinfunction "+_+") (pintype "passive"))
      (node (ref "C6") (pin "1") (pinfunction "1_1") (pintype "passive"))
      (node (ref "C7") (pin "1") (pinfunction "1_1") (pintype "passive"))
      (node (ref "C9") (pin "1") (pinfunction "1_1") (pintype "passive"))
      (node (ref "IC1") (pin "3") (pinfunction "IN_3") (pintype "input"))
      (node (ref "IC2") (pin "1") (pinfunction "MR_1") (pintype "input"))
      (node (ref "IC2") (pin "2") (pinfunction "VCC_2") (pintype "power_in"))
      (node (ref "IC3") (pin "20") (pinfunction "VDD_20") (pintype "power_in"))
      (node (ref "IC5") (pin "2") (pinfunction "OUT_2") (pintype "passive"))
      (node (ref "J5") (pin "1") (pinfunction "1_1") (pintype "passive"))
      (node (ref "R2") (pin "2") (pinfunction "2_2") (pintype "passive"))
      (node (ref "R22") (pin "1") (pinfunction "1_1") (pintype "passive"))
      (node (ref "R23") (pin "2") (pinfunction "2_2") (pintype "passive"))
      (node (ref "R26") (pin "2") (pinfunction "2_2") (pintype "passive"))
      (node (ref "R3") (pin "2") (pinfunction "2_2") (pintype "passive"))
      (node (ref "R37") (pin "2") (pinfunction "2_2") (pintype "passive"))
      (node (ref "R38") (pin "2") (pinfunction "2_2") (pintype "passive"))
      (node (ref "R7") (pin "2") (pinfunction "2_2") (pintype "passive"))
      (node (ref "SV2") (pin "1") (pinfunction "1_1") (pintype "passive"))
    )
    (net (code "66") (name "VDD") (class "Default")
      (node (ref "C2") (pin "1") (pinfunction "1_1") (pintype "passive"))
      (node (ref "IC1") (pin "2") (pinfunction "OUT_2") (pintype "passive"))
      (node (ref "J1") (pin "VDD") (pinfunction "VDD_VDD") (pintype "power_in"))
      (node (ref "J5") (pin "10") (pinfunction "10_10") (pintype "passive"))
      (node (ref "R1") (pin "1") (pinfunction "1_1") (pintype "passive"))
      (node (ref "R11") (pin "1") (pinfunction "1_1") (pintype "passive"))
      (node (ref "R35") (pin "2") (pinfunction "2_2") (pintype "passive"))
      (node (ref "R36") (pin "2") (pinfunction "2_2") (pintype "passive"))
      (node (ref "SV2") (pin "3") (pinfunction "3_3") (pintype "passive"))
    )
    (net (code "67") (name "unconnected-(IC4A-R2OUT-Pad9)") (class "Default")
      (node (ref "IC4") (pin "9") (pinfunction "R2OUT_9") (pintype "output"))
    )
    (net (code "68") (name "unconnected-(IC4A-T2OUT-Pad7)") (class "Default")
      (node (ref "IC4") (pin "7") (pinfunction "T2OUT_7") (pintype "output"))
    )
  )
)
